# design.net
KiCad netlist of a schematic drawn in Altium Designer
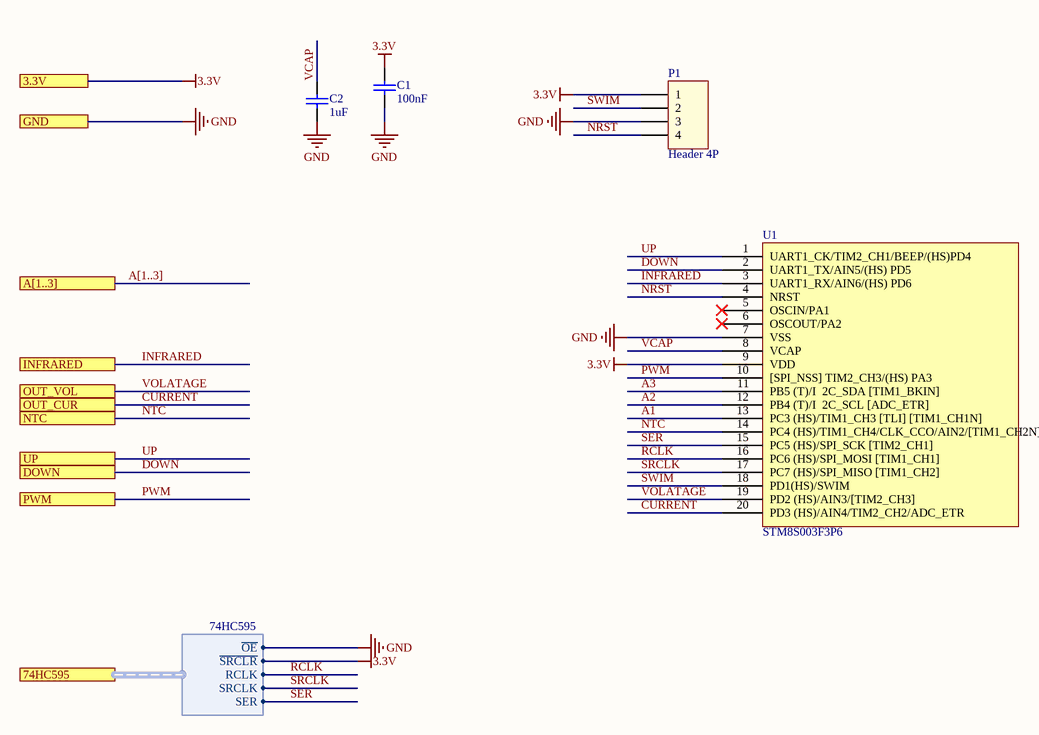
[diagram p0: 主控模块.SchDoc]

(export (version "E")
  (design (tool "Eeschema 10.0.6"))
  (components
    (comp (ref "C1")
      (value "100nF")
      (footprint "LC-0603_C")
      (description "贴片电容")
      (libsource (lib "Miscellaneous Devices LC") (part "0603 100nF (104) 10% 50V"))
    )
    (comp (ref "C2")
      (value "1uF")
      (footprint "LC-0603_C")
      (description "贴片电容")
      (libsource (lib "Miscellaneous Devices LC") (part "0603 1uF (105) 10% 50V"))
    )
    (comp (ref "P1")
      (value "Header 4P")
      (footprint "2.54mm_4P")
      (libsource (lib "user_Library") (part "Header 4P"))
    )
    (comp (ref "U1")
      (value "STM8S003F3P6")
      (footprint "LC-TSSOP-20")
      (description "MCU")
      (libsource (lib "Miscellaneous Devices LC") (part "STM8S003F3P6"))
    )
  )
  (nets
    (net (code "2") (name "/A1") (class "Default")
      (node (ref "U1") (pin "13") (pinfunction "PC3_(HS)/TIM1_CH3_[TLI]_[TIM1_CH1N]_13") (pintype "passive"))
    )
    (net (code "3") (name "/A2") (class "Default")
      (node (ref "U1") (pin "12") (pinfunction "PB4_(T)/I__2C_SCL_[ADC_ETR]_12") (pintype "passive"))
    )
    (net (code "4") (name "/A3") (class "Default")
      (node (ref "U1") (pin "11") (pinfunction "PB5_(T)/I__2C_SDA_[TIM1_BKIN]_11") (pintype "passive"))
    )
    (net (code "6") (name "/CURRENT") (class "Default")
      (node (ref "U1") (pin "20") (pinfunction "PD3_(HS)/AIN4/TIM2_CH2/ADC_ETR_20") (pintype "passive"))
    )
    (net (code "7") (name "/DOWN") (class "Default")
      (node (ref "U1") (pin "2") (pinfunction "UART1_TX/AIN5/(HS)_PD5_2") (pintype "passive"))
    )
    (net (code "8") (name "/INFRARED") (class "Default")
      (node (ref "U1") (pin "3") (pinfunction "UART1_RX/AIN6/(HS)_PD6_3") (pintype "passive"))
    )
    (net (code "9") (name "/NRST") (class "Default")
      (node (ref "P1") (pin "4") (pinfunction "4_4") (pintype "passive"))
      (node (ref "U1") (pin "4") (pinfunction "NRST_4") (pintype "passive"))
    )
    (net (code "10") (name "/NTC") (class "Default")
      (node (ref "U1") (pin "14") (pinfunction "PC4_(HS)/TIM1_CH4/CLK_CCO/AIN2/[TIM1_CH2N]_14") (pintype "passive"))
    )
    (net (code "11") (name "/PWM") (class "Default")
      (node (ref "U1") (pin "10") (pinfunction "[SPI_NSS]_TIM2_CH3/(HS)_PA3_10") (pintype "passive"))
    )
    (net (code "12") (name "/RCLK") (class "Default")
      (node (ref "U1") (pin "16") (pinfunction "PC6_(HS)/SPI_MOSI_[TIM1_CH1]_16") (pintype "passive"))
    )
    (net (code "13") (name "/SER") (class "Default")
      (node (ref "U1") (pin "15") (pinfunction "PC5_(HS)/SPI_SCK_[TIM2_CH1]_15") (pintype "passive"))
    )
    (net (code "14") (name "/SRCLK") (class "Default")
      (node (ref "U1") (pin "17") (pinfunction "PC7_(HS)/SPI_MISO_[TIM1_CH2]_17") (pintype "passive"))
    )
    (net (code "15") (name "/SWIM") (class "Default")
      (node (ref "P1") (pin "2") (pinfunction "2_2") (pintype "passive"))
      (node (ref "U1") (pin "18") (pinfunction "PD1(HS)/SWIM_18") (pintype "passive"))
    )
    (net (code "16") (name "/UP") (class "Default")
      (node (ref "U1") (pin "1") (pinfunction "UART1_CK/TIM2_CH1/BEEP/(HS)PD4_1") (pintype "passive"))
    )
    (net (code "17") (name "/VCAP") (class "Default")
      (node (ref "C2") (pin "2") (pinfunction "2_2") (pintype "passive"))
      (node (ref "U1") (pin "8") (pinfunction "VCAP_8") (pintype "passive"))
    )
    (net (code "18") (name "/VOLATAGE") (class "Default")
      (node (ref "U1") (pin "19") (pinfunction "PD2_(HS)/AIN3/[TIM2_CH3]_19") (pintype "passive"))
    )
    (net (code "20") (name "3.3V") (class "Default")
      (node (ref "C1") (pin "2") (pinfunction "2_2") (pintype "passive"))
      (node (ref "P1") (pin "1") (pinfunction "1_1") (pintype "passive"))
      (node (ref "U1") (pin "9") (pinfunction "VDD_9") (pintype "passive"))
    )
    (net (code "21") (name "GND") (class "Default")
      (node (ref "C1") (pin "1") (pinfunction "1_1") (pintype "passive"))
      (node (ref "C2") (pin "1") (pinfunction "1_1") (pintype "passive"))
      (node (ref "P1") (pin "3") (pinfunction "3_3") (pintype "passive"))
      (node (ref "U1") (pin "7") (pinfunction "VSS_7") (pintype "passive"))
    )
    (net (code "22") (name "unconnected-(U1-OSCIN{slash}PA1-Pad5)") (class "Default")
      (node (ref "U1") (pin "5") (pinfunction "OSCIN/PA1_5") (pintype "passive+no_connect"))
    )
    (net (code "23") (name "unconnected-(U1-OSCOUT{slash}PA2-Pad6)") (class "Default")
      (node (ref "U1") (pin "6") (pinfunction "OSCOUT/PA2_6") (pintype "passive+no_connect"))
    )
  )
)
